# PICKIT2-Original-WithOut-Memory-1.net
KiCad netlist of a schematic drawn in Altium Designer
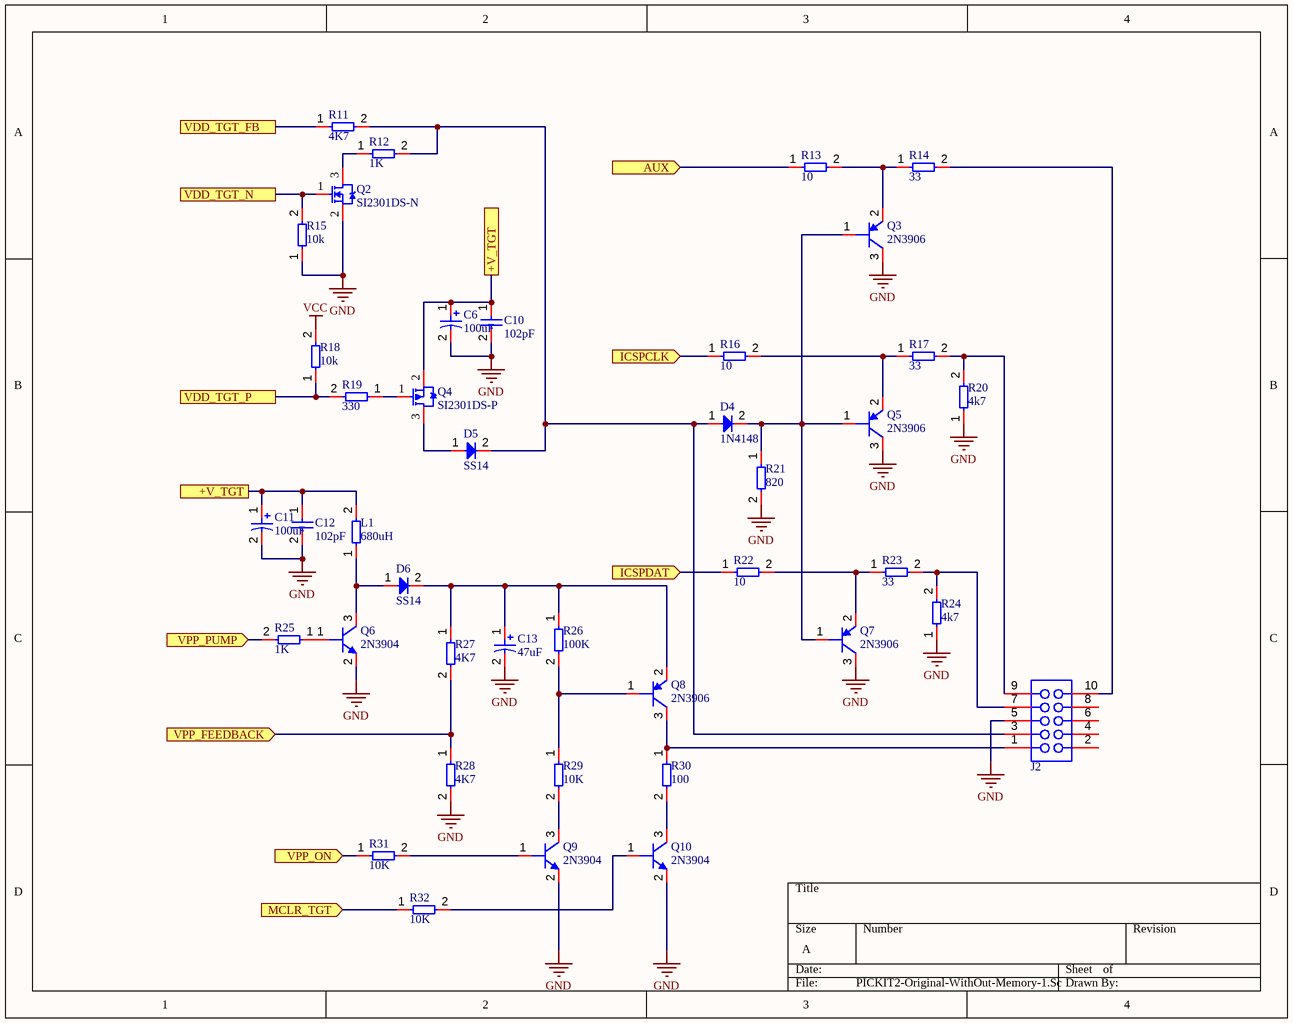
[diagram p0: PICKIT2-Original-WithOut-Memory-1.SchDoc]

(export (version "E")
  (design (tool "Eeschema 10.0.6"))
  (components
    (comp (ref "C6")
      (value "100uF")
      (footprint "CAP_RAD_4mm")
      (libsource (lib "SMDLibrary") (part "Capacitor(Radian)"))
    )
    (comp (ref "C10")
      (value "102pF")
      (footprint "C0805")
      (libsource (lib "SMDLibrary") (part "Capacitors(SMD)"))
    )
    (comp (ref "C11")
      (value "100uF")
      (footprint "CAP_RAD_4mm")
      (libsource (lib "SMDLibrary") (part "Capacitor(Radian)"))
    )
    (comp (ref "C12")
      (value "102pF")
      (footprint "C0805")
      (libsource (lib "SMDLibrary") (part "Capacitors(SMD)"))
    )
    (comp (ref "C13")
      (value "47uF")
      (footprint "CAP_RAD_4mm")
      (libsource (lib "SMDLibrary") (part "Capacitor(Radian)"))
    )
    (comp (ref "D4")
      (value "1N4148")
      (footprint "SOD-80")
      (libsource (lib "SMDLibrary") (part "1N4148 (SOD-80)"))
    )
    (comp (ref "D5")
      (value "SS14")
      (footprint "DO-214AC(SMA)")
      (libsource (lib "SMDLibrary") (part "Diode 1N4007-DO214AC(SMA)"))
    )
    (comp (ref "D6")
      (value "SS14")
      (footprint "DO-214AC(SMA)")
      (libsource (lib "SMDLibrary") (part "Diode 1N4007-DO214AC(SMA)"))
    )
    (comp (ref "J2")
      (value "Header 5x2 TH Pitch 2.54mm")
      (footprint "Header 5x2 TH Pitch 2.54mm")
      (libsource (lib "SMDLibrary") (part "Header 5x2 TH Pitch 2.54mm"))
    )
    (comp (ref "L1")
      (value "680uH")
      (footprint "RES-0.5W-HH-MF")
      (libsource (lib "SMDLibrary") (part "Resistors THD"))
    )
    (comp (ref "Q2")
      (value "SI2301DS-N")
      (footprint "SOT23-3")
      (libsource (lib "SMDLibrary") (part "SI2301DS-N"))
    )
    (comp (ref "Q3") (value "2N3906") (footprint "SOT23-3") (libsource (lib "SMDLibrary") (part "2N3906")))
    (comp (ref "Q4") (value "SI2301DS-P") (libsource (lib "SMDLibrary") (part "SI2301DS-P")))
    (comp (ref "Q5") (value "2N3906") (footprint "SOT23-3") (libsource (lib "SMDLibrary") (part "2N3906")))
    (comp (ref "Q6") (value "2N3904") (footprint "SOT23-3") (libsource (lib "SMDLibrary") (part "2N3904")))
    (comp (ref "Q7") (value "2N3906") (footprint "SOT23-3") (libsource (lib "SMDLibrary") (part "2N3906")))
    (comp (ref "Q8") (value "2N3906") (footprint "SOT23-3") (libsource (lib "SMDLibrary") (part "2N3906")))
    (comp (ref "Q9") (value "2N3904") (footprint "SOT23-3") (libsource (lib "SMDLibrary") (part "2N3904")))
    (comp (ref "Q10") (value "2N3904") (footprint "SOT23-3") (libsource (lib "SMDLibrary") (part "2N3904")))
    (comp (ref "R11") (value "4K7") (footprint "R0805") (libsource (lib "SMDLibrary") (part "Resistor SMD")))
    (comp (ref "R12") (value "1K") (footprint "R0805") (libsource (lib "SMDLibrary") (part "Resistor SMD")))
    (comp (ref "R13") (value "10") (footprint "R0805") (libsource (lib "SMDLibrary") (part "Resistor SMD")))
    (comp (ref "R14") (value "33") (footprint "R0805") (libsource (lib "SMDLibrary") (part "Resistor SMD")))
    (comp (ref "R15") (value "10k") (footprint "R0805") (libsource (lib "") (part "Resistor SMD_3")))
    (comp (ref "R16") (value "10") (footprint "R0805") (libsource (lib "SMDLibrary") (part "Resistor SMD")))
    (comp (ref "R17") (value "33") (footprint "R0805") (libsource (lib "SMDLibrary") (part "Resistor SMD")))
    (comp (ref "R18") (value "10k") (footprint "R0805") (libsource (lib "") (part "Resistor SMD_3")))
    (comp (ref "R19") (value "330") (footprint "R0805") (libsource (lib "") (part "Resistor SMD_2")))
    (comp (ref "R20") (value "4k7") (footprint "R0805") (libsource (lib "") (part "Resistor SMD_3")))
    (comp (ref "R21") (value "820") (footprint "R0805") (libsource (lib "") (part "Resistor SMD_1")))
    (comp (ref "R22") (value "10") (footprint "R0805") (libsource (lib "SMDLibrary") (part "Resistor SMD")))
    (comp (ref "R23") (value "33") (footprint "R0805") (libsource (lib "SMDLibrary") (part "Resistor SMD")))
    (comp (ref "R24") (value "4k7") (footprint "R0805") (libsource (lib "") (part "Resistor SMD_3")))
    (comp (ref "R25") (value "1K") (footprint "R0805") (libsource (lib "") (part "Resistor SMD_2")))
    (comp (ref "R26") (value "100K") (footprint "R0805") (libsource (lib "") (part "Resistor SMD_1")))
    (comp (ref "R27") (value "4K7") (footprint "R0805") (libsource (lib "") (part "Resistor SMD_1")))
    (comp (ref "R28") (value "4K7") (footprint "R0805") (libsource (lib "") (part "Resistor SMD_1")))
    (comp (ref "R29") (value "10K") (footprint "R0805") (libsource (lib "") (part "Resistor SMD_1")))
    (comp (ref "R30") (value "100") (footprint "R0805") (libsource (lib "") (part "Resistor SMD_1")))
    (comp (ref "R31") (value "10K") (footprint "R0805") (libsource (lib "SMDLibrary") (part "Resistor SMD")))
    (comp (ref "R32") (value "10K") (footprint "R0805") (libsource (lib "SMDLibrary") (part "Resistor SMD")))
  )
  (nets
    (net (code "1") (name "/+V_TGT") (class "Default")
      (node (ref "C10") (pin "1") (pinfunction "1_1") (pintype "passive"))
      (node (ref "C11") (pin "1") (pinfunction "1_1") (pintype "passive"))
      (node (ref "C12") (pin "1") (pinfunction "1_1") (pintype "passive"))
      (node (ref "C6") (pin "1") (pinfunction "1_1") (pintype "passive"))
      (node (ref "L1") (pin "2") (pinfunction "2_2") (pintype "passive"))
      (node (ref "Q4") (pin "2") (pinfunction "S_2") (pintype "passive"))
    )
    (net (code "2") (name "/AUX") (class "Default")
      (node (ref "R13") (pin "1") (pinfunction "1_1") (pintype "passive"))
    )
    (net (code "3") (name "/ICSPCLK") (class "Default")
      (node (ref "R16") (pin "1") (pinfunction "1_1") (pintype "passive"))
    )
    (net (code "4") (name "/ICSPDAT") (class "Default")
      (node (ref "R22") (pin "1") (pinfunction "1_1") (pintype "passive"))
    )
    (net (code "5") (name "/MCLR_TGT") (class "Default")
      (node (ref "R32") (pin "1") (pinfunction "1_1") (pintype "passive"))
    )
    (net (code "6") (name "/VDD_TGT_FB") (class "Default")
      (node (ref "R11") (pin "1") (pinfunction "1_1") (pintype "passive"))
    )
    (net (code "7") (name "/VDD_TGT_N") (class "Default")
      (node (ref "Q2") (pin "1") (pinfunction "G_1") (pintype "passive"))
      (node (ref "R15") (pin "2") (pinfunction "2_2") (pintype "passive"))
    )
    (net (code "8") (name "/VDD_TGT_P") (class "Default")
      (node (ref "R18") (pin "1") (pinfunction "1_1") (pintype "passive"))
      (node (ref "R19") (pin "2") (pinfunction "2_2") (pintype "passive"))
    )
    (net (code "9") (name "/VPP_FEEDBACK") (class "Default")
      (node (ref "R27") (pin "2") (pinfunction "2_2") (pintype "passive"))
      (node (ref "R28") (pin "1") (pinfunction "1_1") (pintype "passive"))
    )
    (net (code "10") (name "/VPP_ON") (class "Default")
      (node (ref "R31") (pin "1") (pinfunction "1_1") (pintype "passive"))
    )
    (net (code "11") (name "/VPP_PUMP") (class "Default")
      (node (ref "R25") (pin "2") (pinfunction "2_2") (pintype "passive"))
    )
    (net (code "12") (name "GND") (class "Default")
      (node (ref "C10") (pin "2") (pinfunction "2_2") (pintype "passive"))
      (node (ref "C11") (pin "2") (pinfunction "2_2") (pintype "passive"))
      (node (ref "C12") (pin "2") (pinfunction "2_2") (pintype "passive"))
      (node (ref "C13") (pin "2") (pinfunction "2_2") (pintype "passive"))
      (node (ref "C6") (pin "2") (pinfunction "2_2") (pintype "passive"))
      (node (ref "J2") (pin "5") (pinfunction "5_5") (pintype "passive"))
      (node (ref "Q10") (pin "2") (pinfunction "E_2") (pintype "passive"))
      (node (ref "Q2") (pin "2") (pinfunction "S_2") (pintype "passive"))
      (node (ref "Q3") (pin "3") (pinfunction "C_3") (pintype "passive"))
      (node (ref "Q5") (pin "3") (pinfunction "C_3") (pintype "passive"))
      (node (ref "Q6") (pin "2") (pinfunction "E_2") (pintype "passive"))
      (node (ref "Q7") (pin "3") (pinfunction "C_3") (pintype "passive"))
      (node (ref "Q9") (pin "2") (pinfunction "E_2") (pintype "passive"))
      (node (ref "R15") (pin "1") (pinfunction "1_1") (pintype "passive"))
      (node (ref "R20") (pin "1") (pinfunction "1_1") (pintype "passive"))
      (node (ref "R21") (pin "2") (pinfunction "2_2") (pintype "passive"))
      (node (ref "R24") (pin "1") (pinfunction "1_1") (pintype "passive"))
      (node (ref "R28") (pin "2") (pinfunction "2_2") (pintype "passive"))
    )
    (net (code "13") (name "Net-(D4-Pad1)") (class "Default")
      (node (ref "D4") (pin "1") (pinfunction "1_1") (pintype "passive"))
      (node (ref "D5") (pin "2") (pinfunction "2_2") (pintype "passive"))
      (node (ref "J2") (pin "3") (pinfunction "3_3") (pintype "passive"))
      (node (ref "R11") (pin "2") (pinfunction "2_2") (pintype "passive"))
      (node (ref "R12") (pin "2") (pinfunction "2_2") (pintype "passive"))
    )
    (net (code "14") (name "Net-(J2-Pad7)") (class "Default")
      (node (ref "J2") (pin "7") (pinfunction "7_7") (pintype "passive"))
      (node (ref "R23") (pin "2") (pinfunction "2_2") (pintype "passive"))
      (node (ref "R24") (pin "2") (pinfunction "2_2") (pintype "passive"))
    )
    (net (code "15") (name "Net-(J2-Pad9)") (class "Default")
      (node (ref "J2") (pin "9") (pinfunction "9_9") (pintype "passive"))
      (node (ref "R17") (pin "2") (pinfunction "2_2") (pintype "passive"))
      (node (ref "R20") (pin "2") (pinfunction "2_2") (pintype "passive"))
    )
    (net (code "16") (name "Net-(J2-Pad10)") (class "Default")
      (node (ref "J2") (pin "10") (pinfunction "10_10") (pintype "passive"))
      (node (ref "R14") (pin "2") (pinfunction "2_2") (pintype "passive"))
    )
    (net (code "17") (name "Net-(Q2-D)") (class "Default")
      (node (ref "Q2") (pin "3") (pinfunction "D_3") (pintype "passive"))
      (node (ref "R12") (pin "1") (pinfunction "1_1") (pintype "passive"))
    )
    (net (code "18") (name "Net-(Q3-B)") (class "Default")
      (node (ref "D4") (pin "2") (pinfunction "2_2") (pintype "passive"))
      (node (ref "Q3") (pin "1") (pinfunction "B_1") (pintype "passive"))
      (node (ref "Q5") (pin "1") (pinfunction "B_1") (pintype "passive"))
      (node (ref "Q7") (pin "1") (pinfunction "B_1") (pintype "passive"))
      (node (ref "R21") (pin "1") (pinfunction "1_1") (pintype "passive"))
    )
    (net (code "19") (name "Net-(Q3-E)") (class "Default")
      (node (ref "Q3") (pin "2") (pinfunction "E_2") (pintype "passive"))
      (node (ref "R13") (pin "2") (pinfunction "2_2") (pintype "passive"))
      (node (ref "R14") (pin "1") (pinfunction "1_1") (pintype "passive"))
    )
    (net (code "20") (name "Net-(Q4-D)") (class "Default")
      (node (ref "D5") (pin "1") (pinfunction "1_1") (pintype "passive"))
      (node (ref "Q4") (pin "3") (pinfunction "D_3") (pintype "passive"))
    )
    (net (code "21") (name "Net-(Q4-G)") (class "Default")
      (node (ref "Q4") (pin "1") (pinfunction "G_1") (pintype "passive"))
      (node (ref "R19") (pin "1") (pinfunction "1_1") (pintype "passive"))
    )
    (net (code "22") (name "Net-(Q5-E)") (class "Default")
      (node (ref "Q5") (pin "2") (pinfunction "E_2") (pintype "passive"))
      (node (ref "R16") (pin "2") (pinfunction "2_2") (pintype "passive"))
      (node (ref "R17") (pin "1") (pinfunction "1_1") (pintype "passive"))
    )
    (net (code "23") (name "Net-(Q6-B)") (class "Default")
      (node (ref "Q6") (pin "1") (pinfunction "B_1") (pintype "passive"))
      (node (ref "R25") (pin "1") (pinfunction "1_1") (pintype "passive"))
    )
    (net (code "24") (name "Net-(Q6-C)") (class "Default")
      (node (ref "D6") (pin "1") (pinfunction "1_1") (pintype "passive"))
      (node (ref "L1") (pin "1") (pinfunction "1_1") (pintype "passive"))
      (node (ref "Q6") (pin "3") (pinfunction "C_3") (pintype "passive"))
    )
    (net (code "25") (name "Net-(Q7-E)") (class "Default")
      (node (ref "Q7") (pin "2") (pinfunction "E_2") (pintype "passive"))
      (node (ref "R22") (pin "2") (pinfunction "2_2") (pintype "passive"))
      (node (ref "R23") (pin "1") (pinfunction "1_1") (pintype "passive"))
    )
    (net (code "26") (name "Net-(Q8-B)") (class "Default")
      (node (ref "Q8") (pin "1") (pinfunction "B_1") (pintype "passive"))
      (node (ref "R26") (pin "2") (pinfunction "2_2") (pintype "passive"))
      (node (ref "R29") (pin "1") (pinfunction "1_1") (pintype "passive"))
    )
    (net (code "27") (name "Net-(Q8-C)") (class "Default")
      (node (ref "J2") (pin "1") (pinfunction "1_1") (pintype "passive"))
      (node (ref "Q8") (pin "3") (pinfunction "C_3") (pintype "passive"))
      (node (ref "R30") (pin "1") (pinfunction "1_1") (pintype "passive"))
    )
    (net (code "28") (name "Net-(Q8-E)") (class "Default")
      (node (ref "C13") (pin "1") (pinfunction "1_1") (pintype "passive"))
      (node (ref "D6") (pin "2") (pinfunction "2_2") (pintype "passive"))
      (node (ref "Q8") (pin "2") (pinfunction "E_2") (pintype "passive"))
      (node (ref "R26") (pin "1") (pinfunction "1_1") (pintype "passive"))
      (node (ref "R27") (pin "1") (pinfunction "1_1") (pintype "passive"))
    )
    (net (code "29") (name "Net-(Q9-B)") (class "Default")
      (node (ref "Q9") (pin "1") (pinfunction "B_1") (pintype "passive"))
      (node (ref "R31") (pin "2") (pinfunction "2_2") (pintype "passive"))
    )
    (net (code "30") (name "Net-(Q9-C)") (class "Default")
      (node (ref "Q9") (pin "3") (pinfunction "C_3") (pintype "passive"))
      (node (ref "R29") (pin "2") (pinfunction "2_2") (pintype "passive"))
    )
    (net (code "31") (name "Net-(Q10-B)") (class "Default")
      (node (ref "Q10") (pin "1") (pinfunction "B_1") (pintype "passive"))
      (node (ref "R32") (pin "2") (pinfunction "2_2") (pintype "passive"))
    )
    (net (code "32") (name "Net-(Q10-C)") (class "Default")
      (node (ref "Q10") (pin "3") (pinfunction "C_3") (pintype "passive"))
      (node (ref "R30") (pin "2") (pinfunction "2_2") (pintype "passive"))
    )
    (net (code "33") (name "VCC") (class "Default")
      (node (ref "R18") (pin "2") (pinfunction "2_2") (pintype "passive"))
    )
    (net (code "34") (name "unconnected-(J2-Pad2)") (class "Default")
      (node (ref "J2") (pin "2") (pinfunction "2_2") (pintype "passive"))
    )
    (net (code "35") (name "unconnected-(J2-Pad4)") (class "Default")
      (node (ref "J2") (pin "4") (pinfunction "4_4") (pintype "passive"))
    )
    (net (code "36") (name "unconnected-(J2-Pad6)") (class "Default")
      (node (ref "J2") (pin "6") (pinfunction "6_6") (pintype "passive"))
    )
    (net (code "37") (name "unconnected-(J2-Pad8)") (class "Default")
      (node (ref "J2") (pin "8") (pinfunction "8_8") (pintype "passive"))
    )
  )
)
